# RS422.net
KiCad netlist of a schematic drawn in Altium Designer
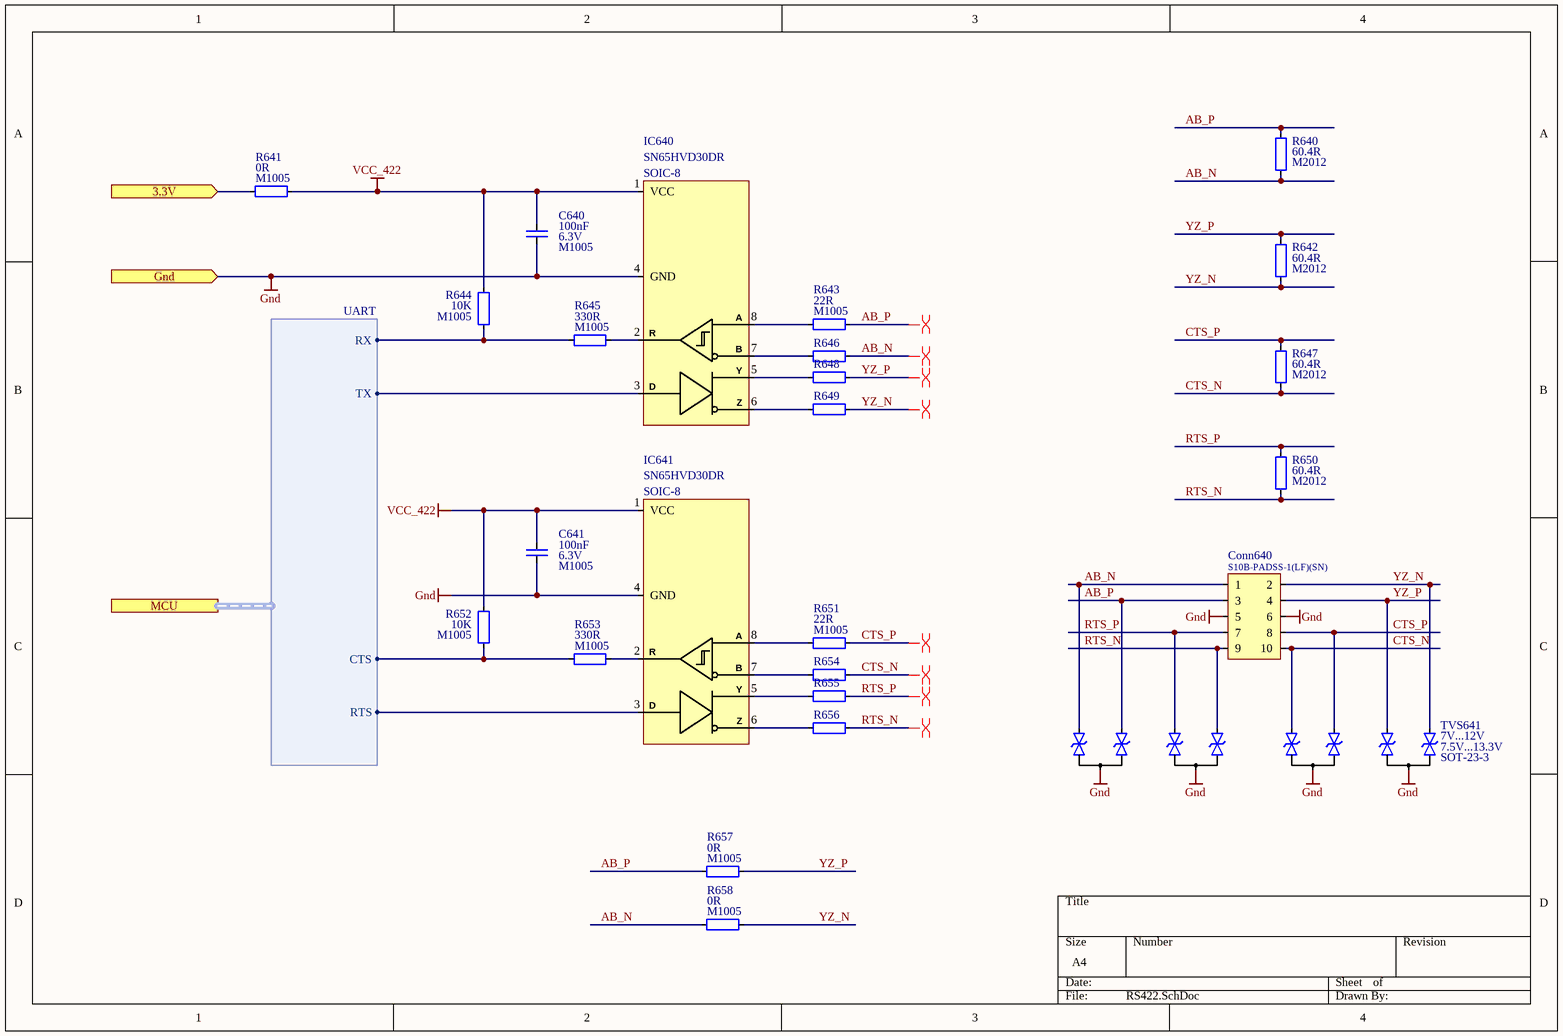
[diagram p0: RS422.SchDoc]

(export (version "E")
  (design (tool "Eeschema 10.0.6"))
  (components
    (comp (ref "C640")
      (value "100nF")
      (footprint "Capacitor_Ceramic_M1005_I0402")
      (description "Cap, Cer, 100nF, 6.3V, M1005")
      (fields
        (field (name "VOLTAGE") "6.3V")
        (field (name "MANUFACTURER PART NUMBER") "04026D104KAT4A")
        (field (name "MANUFACTURER") "Kyocera")
        (field (name "PACKAGE") "M1005")
      )
      (libsource (lib "Capacitor") (part "Capacitor_Ceramic"))
    )
    (comp (ref "C641")
      (value "100nF")
      (footprint "Capacitor_Ceramic_M1005_I0402")
      (description "Cap, Cer, 100nF, 6.3V, M1005")
      (fields
        (field (name "VOLTAGE") "6.3V")
        (field (name "MANUFACTURER PART NUMBER") "04026D104KAT4A")
        (field (name "MANUFACTURER") "Kyocera")
        (field (name "PACKAGE") "M1005")
      )
      (libsource (lib "Capacitor") (part "Capacitor_Ceramic"))
    )
    (comp (ref "Conn640")
      (value "Connector - 10P")
      (footprint "Connector, S10B-PADSS-1")
      (description "Conn, JST, 10P, TH, PAD, Side Entry")
      (fields
        (field (name "MANUFACTURER") "JST")
        (field (name "MANUFACTURER PART NUMBER") "S10B-PADSS-1(LF)(SN)")
      )
      (libsource (lib "Connector - JST") (part "Connector - 10P"))
    )
    (comp (ref "IC640")
      (value "RS422 - Texas, SN65HVD30D")
      (footprint "SOIC-8, NB")
      (description "IC, Interface, RS422, SOIC-8")
      (fields
        (field (name "MANUFACTURER") "Texas")
        (field (name "MANUFACTURER PART NUMBER") "SN65HVD30DR")
        (field (name "PACKAGE") "SOIC-8")
      )
      (libsource (lib "IC - Interface") (part "RS422 - Texas, SN65HVD30D"))
    )
    (comp (ref "IC641")
      (value "RS422 - Texas, SN65HVD30D")
      (footprint "SOIC-8, NB")
      (description "IC, Interface, RS422, SOIC-8")
      (fields
        (field (name "MANUFACTURER") "Texas")
        (field (name "MANUFACTURER PART NUMBER") "SN65HVD30DR")
        (field (name "PACKAGE") "SOIC-8")
      )
      (libsource (lib "IC - Interface") (part "RS422 - Texas, SN65HVD30D"))
    )
    (comp (ref "R640")
      (value "60.4R")
      (footprint "Resistor_Smd_M2012_I0805")
      (description "Res, 60.4R, 1%, M1005")
      (fields
        (field (name "TOLERANCE") "1%")
        (field (name "MANUFACTURER") "Yageo")
        (field (name "PACKAGE") "M2012")
      )
      (libsource (lib "Resistor") (part "Resistor"))
    )
    (comp (ref "R641")
      (value "0R")
      (footprint "Resistor_Smd_M1005_I0402")
      (description "Res, 0R, M1005")
      (fields
        (field (name "MANUFACTURER") "Yageo")
        (field (name "MANUFACTURER PART NUMBER") "RC0402FR-070RL")
        (field (name "PACKAGE") "M1005")
      )
      (libsource (lib "Resistor") (part "Resistor"))
    )
    (comp (ref "R642")
      (value "60.4R")
      (footprint "Resistor_Smd_M2012_I0805")
      (description "Res, 60.4R, 1%, M1005")
      (fields
        (field (name "TOLERANCE") "1%")
        (field (name "MANUFACTURER") "Yageo")
        (field (name "PACKAGE") "M2012")
      )
      (libsource (lib "Resistor") (part "Resistor"))
    )
    (comp (ref "R643")
      (value "22R")
      (footprint "Resistor_Smd_M1005_I0402")
      (description "Res, 22R, 1%, M1005")
      (fields
        (field (name "TOLERANCE") "1%")
        (field (name "MANUFACTURER") "Yageo")
        (field (name "PACKAGE") "M1005")
      )
      (libsource (lib "Resistor") (part "Resistor"))
    )
    (comp (ref "R644")
      (value "10K")
      (footprint "Resistor_Smd_M1005_I0402")
      (description "Res, 10K, 1%, M1005")
      (fields
        (field (name "TOLERANCE") "1%")
        (field (name "MANUFACTURER") "Yageo")
        (field (name "PACKAGE") "M1005")
      )
      (libsource (lib "Resistor") (part "Resistor"))
    )
    (comp (ref "R645")
      (value "330R")
      (footprint "Resistor_Smd_M1005_I0402")
      (description "Res, 330R, 1%, M1005")
      (fields
        (field (name "TOLERANCE") "1%")
        (field (name "MANUFACTURER") "Yageo")
        (field (name "PACKAGE") "M1005")
      )
      (libsource (lib "Resistor") (part "Resistor"))
    )
    (comp (ref "R646")
      (value "Resistor")
      (footprint "Resistor_Smd_M1005_I0402")
      (description "Res, 22R, 1%, M1005")
      (fields (field (name "TOLERANCE") "1%") (field (name "MANUFACTURER") "Yageo"))
      (libsource (lib "Resistor") (part "Resistor"))
    )
    (comp (ref "R647")
      (value "60.4R")
      (footprint "Resistor_Smd_M2012_I0805")
      (description "Res, 60.4R, 1%, M1005")
      (fields
        (field (name "TOLERANCE") "1%")
        (field (name "MANUFACTURER") "Yageo")
        (field (name "PACKAGE") "M2012")
      )
      (libsource (lib "Resistor") (part "Resistor"))
    )
    (comp (ref "R648")
      (value "Resistor")
      (footprint "Resistor_Smd_M1005_I0402")
      (description "Res, 22R, 1%, M1005")
      (fields (field (name "TOLERANCE") "1%") (field (name "MANUFACTURER") "Yageo"))
      (libsource (lib "Resistor") (part "Resistor"))
    )
    (comp (ref "R649")
      (value "Resistor")
      (footprint "Resistor_Smd_M1005_I0402")
      (description "Res, 22R, 1%, M1005")
      (fields (field (name "TOLERANCE") "1%") (field (name "MANUFACTURER") "Yageo"))
      (libsource (lib "Resistor") (part "Resistor"))
    )
    (comp (ref "R650")
      (value "60.4R")
      (footprint "Resistor_Smd_M2012_I0805")
      (description "Res, 60.4R, 1%, M1005")
      (fields
        (field (name "TOLERANCE") "1%")
        (field (name "MANUFACTURER") "Yageo")
        (field (name "PACKAGE") "M2012")
      )
      (libsource (lib "Resistor") (part "Resistor"))
    )
    (comp (ref "R651")
      (value "22R")
      (footprint "Resistor_Smd_M1005_I0402")
      (description "Res, 22R, 1%, M1005")
      (fields
        (field (name "TOLERANCE") "1%")
        (field (name "MANUFACTURER") "Yageo")
        (field (name "PACKAGE") "M1005")
      )
      (libsource (lib "Resistor") (part "Resistor"))
    )
    (comp (ref "R652")
      (value "10K")
      (footprint "Resistor_Smd_M1005_I0402")
      (description "Res, 10K, 1%, M1005")
      (fields
        (field (name "TOLERANCE") "1%")
        (field (name "MANUFACTURER") "Yageo")
        (field (name "PACKAGE") "M1005")
      )
      (libsource (lib "Resistor") (part "Resistor"))
    )
    (comp (ref "R653")
      (value "330R")
      (footprint "Resistor_Smd_M1005_I0402")
      (description "Res, 330R, 1%, M1005")
      (fields
        (field (name "TOLERANCE") "1%")
        (field (name "MANUFACTURER") "Yageo")
        (field (name "PACKAGE") "M1005")
      )
      (libsource (lib "Resistor") (part "Resistor"))
    )
    (comp (ref "R654")
      (value "Resistor")
      (footprint "Resistor_Smd_M1005_I0402")
      (description "Res, 22R, 1%, M1005")
      (fields (field (name "TOLERANCE") "1%") (field (name "MANUFACTURER") "Yageo"))
      (libsource (lib "Resistor") (part "Resistor"))
    )
    (comp (ref "R655")
      (value "Resistor")
      (footprint "Resistor_Smd_M1005_I0402")
      (description "Res, 22R, 1%, M1005")
      (fields (field (name "TOLERANCE") "1%") (field (name "MANUFACTURER") "Yageo"))
      (libsource (lib "Resistor") (part "Resistor"))
    )
    (comp (ref "R656")
      (value "Resistor")
      (footprint "Resistor_Smd_M1005_I0402")
      (description "Res, 22R, 1%, M1005")
      (fields (field (name "TOLERANCE") "1%") (field (name "MANUFACTURER") "Yageo"))
      (libsource (lib "Resistor") (part "Resistor"))
    )
    (comp (ref "R657")
      (value "0R")
      (footprint "Resistor_Smd_M1005_I0402")
      (description "Res, 0R, M1005")
      (fields
        (field (name "MANUFACTURER") "Yageo")
        (field (name "MANUFACTURER PART NUMBER") "RC0402FR-070RL")
        (field (name "PACKAGE") "M1005")
      )
      (libsource (lib "Resistor") (part "Resistor"))
    )
    (comp (ref "R658")
      (value "0R")
      (footprint "Resistor_Smd_M1005_I0402")
      (description "Res, 0R, M1005")
      (fields
        (field (name "MANUFACTURER") "Yageo")
        (field (name "MANUFACTURER PART NUMBER") "RC0402FR-070RL")
        (field (name "PACKAGE") "M1005")
      )
      (libsource (lib "Resistor") (part "Resistor"))
    )
    (comp (ref "TVS640")
      (value "Diode_Tvs_2P_Bidirectional")
      (footprint "Diode_SOT-23-3_2P_Bidirectional_Type_1")
      (description "TVS, 2P, Bidirectional, 7V/12V, SOT-23-3")
      (fields
        (field (name "MANUFACTURER PART NUMBER") "CDSOT23-SM712")
        (field (name "MANUFACTURER") "Bourns")
      )
      (libsource (lib "Diode") (part "Diode_Tvs_2P_Bidirectional"))
    )
    (comp (ref "TVS641")
      (value "Diode_Tvs_2P_Bidirectional")
      (footprint "Diode_SOT-23-3_2P_Bidirectional_Type_1")
      (description "TVS, 2P, Bidirectional, 7V/12V, SOT-23-3")
      (fields
        (field (name "MANUFACTURER PART NUMBER") "CDSOT23-SM712")
        (field (name "MANUFACTURER") "Bourns")
        (field (name "VOLTAGE, BREAK DOWN") "7.5V...13.3V")
        (field (name "VOLTAGE, STAND OFF") "7V...12V")
        (field (name "PACKAGE") "SOT-23-3")
      )
      (libsource (lib "Diode") (part "Diode_Tvs_2P_Bidirectional"))
    )
    (comp (ref "TVS642")
      (value "Diode_Tvs_2P_Bidirectional")
      (footprint "Diode_SOT-23-3_2P_Bidirectional_Type_1")
      (description "TVS, 2P, Bidirectional, 7V/12V, SOT-23-3")
      (fields
        (field (name "MANUFACTURER PART NUMBER") "CDSOT23-SM712")
        (field (name "MANUFACTURER") "Bourns")
      )
      (libsource (lib "Diode") (part "Diode_Tvs_2P_Bidirectional"))
    )
    (comp (ref "TVS643")
      (value "Diode_Tvs_2P_Bidirectional")
      (footprint "Diode_SOT-23-3_2P_Bidirectional_Type_1")
      (description "TVS, 2P, Bidirectional, 7V/12V, SOT-23-3")
      (fields
        (field (name "MANUFACTURER PART NUMBER") "CDSOT23-SM712")
        (field (name "MANUFACTURER") "Bourns")
      )
      (libsource (lib "Diode") (part "Diode_Tvs_2P_Bidirectional"))
    )
  )
  (nets
    (net (code "2") (name "/3.3V") (class "Default")
      (node (ref "R641") (pin "1") (pinfunction "1_1") (pintype "passive"))
    )
    (net (code "3") (name "/AB_N") (class "Default")
      (node (ref "Conn640") (pin "1") (pinfunction "1_1") (pintype "passive"))
      (node (ref "R640") (pin "2") (pinfunction "2_2") (pintype "passive"))
      (node (ref "R646") (pin "2") (pinfunction "2_2") (pintype "passive"))
      (node (ref "R658") (pin "1") (pinfunction "1_1") (pintype "passive"))
      (node (ref "TVS642") (pin "D1") (pinfunction "D1_D1") (pintype "passive"))
    )
    (net (code "4") (name "/AB_P") (class "Default")
      (node (ref "Conn640") (pin "3") (pinfunction "3_3") (pintype "passive"))
      (node (ref "R640") (pin "1") (pinfunction "1_1") (pintype "passive"))
      (node (ref "R643") (pin "2") (pinfunction "2_2") (pintype "passive"))
      (node (ref "R657") (pin "1") (pinfunction "1_1") (pintype "passive"))
      (node (ref "TVS642") (pin "D2") (pinfunction "D2_D2") (pintype "passive"))
    )
    (net (code "5") (name "/CTS") (class "Default")
      (node (ref "R652") (pin "1") (pinfunction "1_1") (pintype "passive"))
      (node (ref "R653") (pin "1") (pinfunction "1_1") (pintype "passive"))
    )
    (net (code "6") (name "/CTS_N") (class "Default")
      (node (ref "Conn640") (pin "10") (pinfunction "10_10") (pintype "passive"))
      (node (ref "R647") (pin "2") (pinfunction "2_2") (pintype "passive"))
      (node (ref "R654") (pin "2") (pinfunction "2_2") (pintype "passive"))
      (node (ref "TVS643") (pin "D1") (pinfunction "D1_D1") (pintype "passive"))
    )
    (net (code "7") (name "/CTS_P") (class "Default")
      (node (ref "Conn640") (pin "8") (pinfunction "8_8") (pintype "passive"))
      (node (ref "R647") (pin "1") (pinfunction "1_1") (pintype "passive"))
      (node (ref "R651") (pin "2") (pinfunction "2_2") (pintype "passive"))
      (node (ref "TVS643") (pin "D2") (pinfunction "D2_D2") (pintype "passive"))
    )
    (net (code "8") (name "/RTS") (class "Default")
      (node (ref "IC641") (pin "3") (pinfunction "D_3") (pintype "passive"))
    )
    (net (code "9") (name "/RTS_N") (class "Default")
      (node (ref "Conn640") (pin "9") (pinfunction "9_9") (pintype "passive"))
      (node (ref "R650") (pin "2") (pinfunction "2_2") (pintype "passive"))
      (node (ref "R656") (pin "2") (pinfunction "2_2") (pintype "passive"))
      (node (ref "TVS640") (pin "D2") (pinfunction "D2_D2") (pintype "passive"))
    )
    (net (code "10") (name "/RTS_P") (class "Default")
      (node (ref "Conn640") (pin "7") (pinfunction "7_7") (pintype "passive"))
      (node (ref "R650") (pin "1") (pinfunction "1_1") (pintype "passive"))
      (node (ref "R655") (pin "2") (pinfunction "2_2") (pintype "passive"))
      (node (ref "TVS640") (pin "D1") (pinfunction "D1_D1") (pintype "passive"))
    )
    (net (code "11") (name "/RX") (class "Default")
      (node (ref "R644") (pin "1") (pinfunction "1_1") (pintype "passive"))
      (node (ref "R645") (pin "1") (pinfunction "1_1") (pintype "passive"))
    )
    (net (code "12") (name "/TX") (class "Default")
      (node (ref "IC640") (pin "3") (pinfunction "D_3") (pintype "passive"))
    )
    (net (code "13") (name "/YZ_N") (class "Default")
      (node (ref "Conn640") (pin "2") (pinfunction "2_2") (pintype "passive"))
      (node (ref "R642") (pin "2") (pinfunction "2_2") (pintype "passive"))
      (node (ref "R649") (pin "2") (pinfunction "2_2") (pintype "passive"))
      (node (ref "R658") (pin "2") (pinfunction "2_2") (pintype "passive"))
      (node (ref "TVS641") (pin "D2") (pinfunction "D2_D2") (pintype "passive"))
    )
    (net (code "14") (name "/YZ_P") (class "Default")
      (node (ref "Conn640") (pin "4") (pinfunction "4_4") (pintype "passive"))
      (node (ref "R642") (pin "1") (pinfunction "1_1") (pintype "passive"))
      (node (ref "R648") (pin "2") (pinfunction "2_2") (pintype "passive"))
      (node (ref "R657") (pin "2") (pinfunction "2_2") (pintype "passive"))
      (node (ref "TVS641") (pin "D1") (pinfunction "D1_D1") (pintype "passive"))
    )
    (net (code "16") (name "Gnd") (class "Default")
      (node (ref "C640") (pin "2") (pinfunction "2_2") (pintype "passive"))
      (node (ref "C641") (pin "2") (pinfunction "2_2") (pintype "passive"))
      (node (ref "Conn640") (pin "5") (pinfunction "5_5") (pintype "passive"))
      (node (ref "Conn640") (pin "6") (pinfunction "6_6") (pintype "passive"))
      (node (ref "IC640") (pin "4") (pinfunction "GND_4") (pintype "passive"))
      (node (ref "IC641") (pin "4") (pinfunction "GND_4") (pintype "passive"))
      (node (ref "TVS640") (pin "Common") (pinfunction "Common_Common") (pintype "passive"))
      (node (ref "TVS641") (pin "Common") (pinfunction "Common_Common") (pintype "passive"))
      (node (ref "TVS642") (pin "Common") (pinfunction "Common_Common") (pintype "passive"))
      (node (ref "TVS643") (pin "Common") (pinfunction "Common_Common") (pintype "passive"))
    )
    (net (code "17") (name "Net-(IC640-A)") (class "Default")
      (node (ref "IC640") (pin "8") (pinfunction "A_8") (pintype "passive"))
      (node (ref "R643") (pin "1") (pinfunction "1_1") (pintype "passive"))
    )
    (net (code "18") (name "Net-(IC640-B)") (class "Default")
      (node (ref "IC640") (pin "7") (pinfunction "B_7") (pintype "passive"))
      (node (ref "R646") (pin "1") (pinfunction "1_1") (pintype "passive"))
    )
    (net (code "19") (name "Net-(IC640-R)") (class "Default")
      (node (ref "IC640") (pin "2") (pinfunction "R_2") (pintype "passive"))
      (node (ref "R645") (pin "2") (pinfunction "2_2") (pintype "passive"))
    )
    (net (code "20") (name "Net-(IC640-Y)") (class "Default")
      (node (ref "IC640") (pin "5") (pinfunction "Y_5") (pintype "passive"))
      (node (ref "R648") (pin "1") (pinfunction "1_1") (pintype "passive"))
    )
    (net (code "21") (name "Net-(IC640-Z)") (class "Default")
      (node (ref "IC640") (pin "6") (pinfunction "Z_6") (pintype "passive"))
      (node (ref "R649") (pin "1") (pinfunction "1_1") (pintype "passive"))
    )
    (net (code "22") (name "Net-(IC641-A)") (class "Default")
      (node (ref "IC641") (pin "8") (pinfunction "A_8") (pintype "passive"))
      (node (ref "R651") (pin "1") (pinfunction "1_1") (pintype "passive"))
    )
    (net (code "23") (name "Net-(IC641-B)") (class "Default")
      (node (ref "IC641") (pin "7") (pinfunction "B_7") (pintype "passive"))
      (node (ref "R654") (pin "1") (pinfunction "1_1") (pintype "passive"))
    )
    (net (code "24") (name "Net-(IC641-R)") (class "Default")
      (node (ref "IC641") (pin "2") (pinfunction "R_2") (pintype "passive"))
      (node (ref "R653") (pin "2") (pinfunction "2_2") (pintype "passive"))
    )
    (net (code "25") (name "Net-(IC641-Y)") (class "Default")
      (node (ref "IC641") (pin "5") (pinfunction "Y_5") (pintype "passive"))
      (node (ref "R655") (pin "1") (pinfunction "1_1") (pintype "passive"))
    )
    (net (code "26") (name "Net-(IC641-Z)") (class "Default")
      (node (ref "IC641") (pin "6") (pinfunction "Z_6") (pintype "passive"))
      (node (ref "R656") (pin "1") (pinfunction "1_1") (pintype "passive"))
    )
    (net (code "27") (name "VCC_422") (class "Default")
      (node (ref "C640") (pin "1") (pinfunction "1_1") (pintype "passive"))
      (node (ref "C641") (pin "1") (pinfunction "1_1") (pintype "passive"))
      (node (ref "IC640") (pin "1") (pinfunction "VCC_1") (pintype "passive"))
      (node (ref "IC641") (pin "1") (pinfunction "VCC_1") (pintype "passive"))
      (node (ref "R641") (pin "2") (pinfunction "2_2") (pintype "passive"))
      (node (ref "R644") (pin "2") (pinfunction "2_2") (pintype "passive"))
      (node (ref "R652") (pin "2") (pinfunction "2_2") (pintype "passive"))
    )
  )
)
